# 10_NTC_TEMPSENSOR.net
KiCad netlist of a schematic drawn in Altium Designer
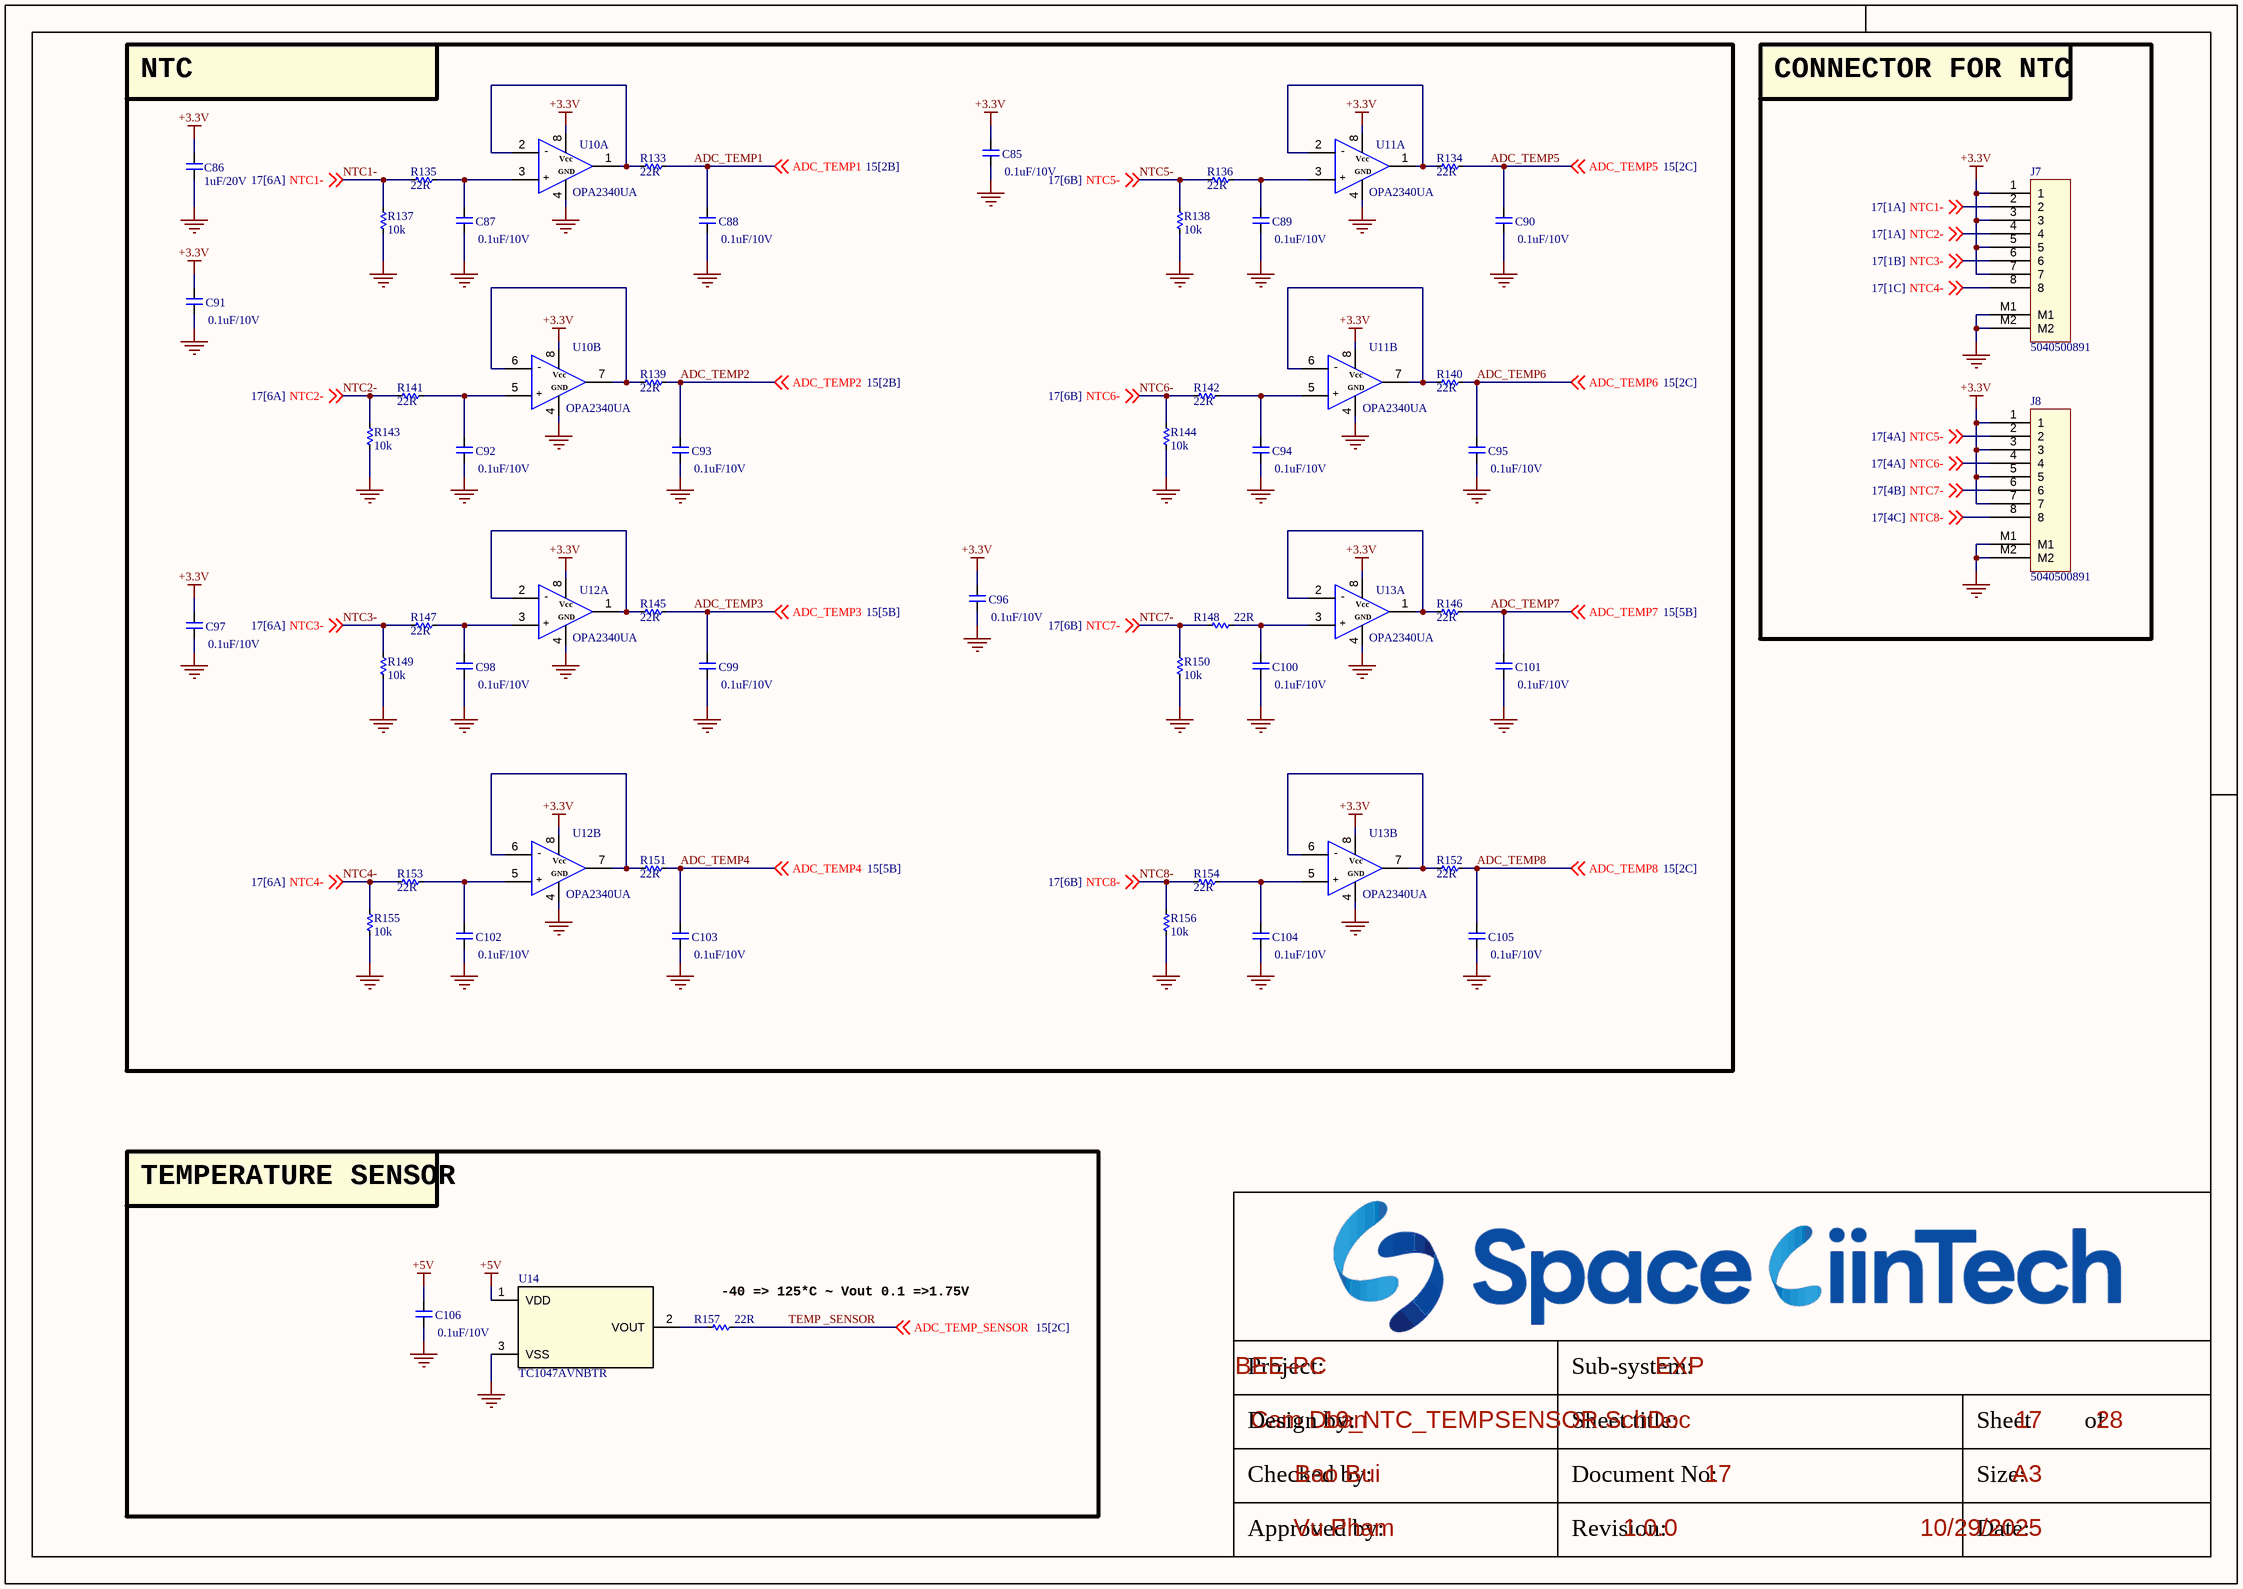
[diagram p0: 10_NTC_TEMPSENSOR.SchDoc]

(export (version "E")
  (design (tool "Eeschema 10.0.6"))
  (components
    (comp (ref "C85")
      (value "0.1uF/10V")
      (footprint "CAP_C_1005X60")
      (description "CAP CHIP")
      (libsource (lib "LABLIB") (part "_CAP_C_2"))
    )
    (comp (ref "C86")
      (value "1uF/20V")
      (footprint "CAP_C_1005X60")
      (description "CAP CHIP")
      (libsource (lib "LABLIB") (part "_CAP_C_2"))
    )
    (comp (ref "C87")
      (value "0.1uF/10V")
      (footprint "CAP_C_1005X60")
      (description "CAP CHIP")
      (libsource (lib "LABLIB") (part "_CAP_C_2"))
    )
    (comp (ref "C88")
      (value "0.1uF/10V")
      (footprint "CAP_C_1005X60")
      (description "CAP CHIP")
      (libsource (lib "LABLIB") (part "_CAP_C_2"))
    )
    (comp (ref "C89")
      (value "0.1uF/10V")
      (footprint "CAP_C_1005X60")
      (description "CAP CHIP")
      (libsource (lib "LABLIB") (part "_CAP_C_2"))
    )
    (comp (ref "C90")
      (value "0.1uF/10V")
      (footprint "CAP_C_1005X60")
      (description "CAP CHIP")
      (libsource (lib "LABLIB") (part "_CAP_C_2"))
    )
    (comp (ref "C91")
      (value "0.1uF/10V")
      (footprint "CAP_C_1005X60")
      (description "CAP CHIP")
      (libsource (lib "LABLIB") (part "_CAP_C_2"))
    )
    (comp (ref "C92")
      (value "0.1uF/10V")
      (footprint "CAP_C_1005X60")
      (description "CAP CHIP")
      (libsource (lib "LABLIB") (part "_CAP_C_2"))
    )
    (comp (ref "C93")
      (value "0.1uF/10V")
      (footprint "CAP_C_1005X60")
      (description "CAP CHIP")
      (libsource (lib "LABLIB") (part "_CAP_C_2"))
    )
    (comp (ref "C94")
      (value "0.1uF/10V")
      (footprint "CAP_C_1005X60")
      (description "CAP CHIP")
      (libsource (lib "LABLIB") (part "_CAP_C_2"))
    )
    (comp (ref "C95")
      (value "0.1uF/10V")
      (footprint "CAP_C_1005X60")
      (description "CAP CHIP")
      (libsource (lib "LABLIB") (part "_CAP_C_2"))
    )
    (comp (ref "C96")
      (value "0.1uF/10V")
      (footprint "CAP_C_1005X60")
      (description "CAP CHIP")
      (libsource (lib "LABLIB") (part "_CAP_C_2"))
    )
    (comp (ref "C97")
      (value "0.1uF/10V")
      (footprint "CAP_C_1005X60")
      (description "CAP CHIP")
      (libsource (lib "LABLIB") (part "_CAP_C_2"))
    )
    (comp (ref "C98")
      (value "0.1uF/10V")
      (footprint "CAP_C_1005X60")
      (description "CAP CHIP")
      (libsource (lib "LABLIB") (part "_CAP_C_2"))
    )
    (comp (ref "C99")
      (value "0.1uF/10V")
      (footprint "CAP_C_1005X60")
      (description "CAP CHIP")
      (libsource (lib "LABLIB") (part "_CAP_C_2"))
    )
    (comp (ref "C100")
      (value "0.1uF/10V")
      (footprint "CAP_C_1005X60")
      (description "CAP CHIP")
      (libsource (lib "LABLIB") (part "_CAP_C_2"))
    )
    (comp (ref "C101")
      (value "0.1uF/10V")
      (footprint "CAP_C_1005X60")
      (description "CAP CHIP")
      (libsource (lib "LABLIB") (part "_CAP_C_2"))
    )
    (comp (ref "C102")
      (value "0.1uF/10V")
      (footprint "CAP_C_1005X60")
      (description "CAP CHIP")
      (libsource (lib "LABLIB") (part "_CAP_C_2"))
    )
    (comp (ref "C103")
      (value "0.1uF/10V")
      (footprint "CAP_C_1005X60")
      (description "CAP CHIP")
      (libsource (lib "LABLIB") (part "_CAP_C_2"))
    )
    (comp (ref "C104")
      (value "0.1uF/10V")
      (footprint "CAP_C_1005X60")
      (description "CAP CHIP")
      (libsource (lib "LABLIB") (part "_CAP_C_2"))
    )
    (comp (ref "C105")
      (value "0.1uF/10V")
      (footprint "CAP_C_1005X60")
      (description "CAP CHIP")
      (libsource (lib "LABLIB") (part "_CAP_C_2"))
    )
    (comp (ref "C106")
      (value "0.1uF/10V")
      (footprint "CAP_C_1005X60")
      (description "CAP CHIP")
      (libsource (lib "LABLIB") (part "_CAP_C_2"))
    )
    (comp (ref "J7")
      (value "5040500891")
      (footprint "MOLEX_5040500891")
      (libsource (lib "LABLIB") (part "Header 8x1_2M"))
    )
    (comp (ref "J8")
      (value "5040500891")
      (footprint "MOLEX_5040500891")
      (libsource (lib "LABLIB") (part "Header 8x1_2M"))
    )
    (comp (ref "R133")
      (value "22R")
      (footprint "RES_C_1005X40")
      (description "RES")
      (libsource (lib "LABLIB") (part "_RES_B_2"))
    )
    (comp (ref "R134")
      (value "22R")
      (footprint "RES_C_1005X40")
      (description "RES")
      (libsource (lib "LABLIB") (part "_RES_B_2"))
    )
    (comp (ref "R135")
      (value "22R")
      (footprint "RES_C_1005X40")
      (description "RES")
      (libsource (lib "LABLIB") (part "_RES_B_2"))
    )
    (comp (ref "R136")
      (value "22R")
      (footprint "RES_C_1005X40")
      (description "RES")
      (libsource (lib "LABLIB") (part "_RES_B_2"))
    )
    (comp (ref "R137")
      (value "10k")
      (footprint "RES_C_1005X40")
      (description "RES")
      (libsource (lib "LABLIB") (part "_RES_B_2"))
    )
    (comp (ref "R138")
      (value "10k")
      (footprint "RES_C_1005X40")
      (description "RES")
      (libsource (lib "LABLIB") (part "_RES_B_2"))
    )
    (comp (ref "R139")
      (value "22R")
      (footprint "RES_C_1005X40")
      (description "RES")
      (libsource (lib "LABLIB") (part "_RES_B_2"))
    )
    (comp (ref "R140")
      (value "22R")
      (footprint "RES_C_1005X40")
      (description "RES")
      (libsource (lib "LABLIB") (part "_RES_B_2"))
    )
    (comp (ref "R141")
      (value "22R")
      (footprint "RES_C_1005X40")
      (description "RES")
      (libsource (lib "LABLIB") (part "_RES_B_2"))
    )
    (comp (ref "R142")
      (value "22R")
      (footprint "RES_C_1005X40")
      (description "RES")
      (libsource (lib "LABLIB") (part "_RES_B_2"))
    )
    (comp (ref "R143")
      (value "10k")
      (footprint "RES_C_1005X40")
      (description "RES")
      (libsource (lib "LABLIB") (part "_RES_B_2"))
    )
    (comp (ref "R144")
      (value "10k")
      (footprint "RES_C_1005X40")
      (description "RES")
      (libsource (lib "LABLIB") (part "_RES_B_2"))
    )
    (comp (ref "R145")
      (value "22R")
      (footprint "RES_C_1005X40")
      (description "RES")
      (libsource (lib "LABLIB") (part "_RES_B_2"))
    )
    (comp (ref "R146")
      (value "22R")
      (footprint "RES_C_1005X40")
      (description "RES")
      (libsource (lib "LABLIB") (part "_RES_B_2"))
    )
    (comp (ref "R147")
      (value "22R")
      (footprint "RES_C_1005X40")
      (description "RES")
      (libsource (lib "LABLIB") (part "_RES_B_2"))
    )
    (comp (ref "R148")
      (value "22R")
      (footprint "RES_C_1005X40")
      (description "RES")
      (libsource (lib "LABLIB") (part "_RES_B_2"))
    )
    (comp (ref "R149")
      (value "10k")
      (footprint "RES_C_1005X40")
      (description "RES")
      (libsource (lib "LABLIB") (part "_RES_B_2"))
    )
    (comp (ref "R150")
      (value "10k")
      (footprint "RES_C_1005X40")
      (description "RES")
      (libsource (lib "LABLIB") (part "_RES_B_2"))
    )
    (comp (ref "R151")
      (value "22R")
      (footprint "RES_C_1005X40")
      (description "RES")
      (libsource (lib "LABLIB") (part "_RES_B_2"))
    )
    (comp (ref "R152")
      (value "22R")
      (footprint "RES_C_1005X40")
      (description "RES")
      (libsource (lib "LABLIB") (part "_RES_B_2"))
    )
    (comp (ref "R153")
      (value "22R")
      (footprint "RES_C_1005X40")
      (description "RES")
      (libsource (lib "LABLIB") (part "_RES_B_2"))
    )
    (comp (ref "R154")
      (value "22R")
      (footprint "RES_C_1005X40")
      (description "RES")
      (libsource (lib "LABLIB") (part "_RES_B_2"))
    )
    (comp (ref "R155")
      (value "10k")
      (footprint "RES_C_1005X40")
      (description "RES")
      (libsource (lib "LABLIB") (part "_RES_B_2"))
    )
    (comp (ref "R156")
      (value "10k")
      (footprint "RES_C_1005X40")
      (description "RES")
      (libsource (lib "LABLIB") (part "_RES_B_2"))
    )
    (comp (ref "R157")
      (value "22R")
      (footprint "RES_C_1005X40")
      (description "RES")
      (libsource (lib "LABLIB") (part "_RES_B_2"))
    )
    (comp (ref "U10")
      (value "OPA2340UA")
      (footprint "SOIC127P602X173-8N")
      (libsource (lib "EXP_HW_V3") (part "OPA2340UA"))
    )
    (comp (ref "U11")
      (value "OPA2340UA")
      (footprint "SOIC127P602X173-8N")
      (libsource (lib "EXP_HW_V3") (part "OPA2340UA"))
    )
    (comp (ref "U12")
      (value "OPA2340UA")
      (footprint "SOIC127P602X173-8N")
      (libsource (lib "EXP_HW_V3") (part "OPA2340UA"))
    )
    (comp (ref "U13")
      (value "OPA2340UA")
      (footprint "SOIC127P602X173-8N")
      (libsource (lib "EXP_HW_V3") (part "OPA2340UA"))
    )
    (comp (ref "U14")
      (value "TC1047AVNBTR")
      (footprint "SOT95P240X120-3N")
      (description "Temperature Sensor Analog, Local -40°C ~ 125°C 10mV/°C SOT-23-3")
      (libsource (lib "LABLIB") (part "IC_SENSOR_TC1047AVNBTR"))
    )
  )
  (nets
    (net (code "1") (name "+3.3V") (class "Default")
      (node (ref "C85") (pin "2") (pinfunction "2_2") (pintype "passive"))
      (node (ref "C86") (pin "2") (pinfunction "2_2") (pintype "passive"))
      (node (ref "C91") (pin "2") (pinfunction "2_2") (pintype "passive"))
      (node (ref "C96") (pin "2") (pinfunction "2_2") (pintype "passive"))
      (node (ref "C97") (pin "2") (pinfunction "2_2") (pintype "passive"))
      (node (ref "J7") (pin "1") (pinfunction "1_1") (pintype "passive"))
      (node (ref "J7") (pin "3") (pinfunction "3_3") (pintype "passive"))
      (node (ref "J7") (pin "5") (pinfunction "5_5") (pintype "passive"))
      (node (ref "J7") (pin "7") (pinfunction "7_7") (pintype "passive"))
      (node (ref "J8") (pin "1") (pinfunction "1_1") (pintype "passive"))
      (node (ref "J8") (pin "3") (pinfunction "3_3") (pintype "passive"))
      (node (ref "J8") (pin "5") (pinfunction "5_5") (pintype "passive"))
      (node (ref "J8") (pin "7") (pinfunction "7_7") (pintype "passive"))
      (node (ref "U10") (pin "8") (pinfunction "8_8") (pintype "passive"))
      (node (ref "U11") (pin "8") (pinfunction "8_8") (pintype "passive"))
      (node (ref "U12") (pin "8") (pinfunction "8_8") (pintype "passive"))
      (node (ref "U13") (pin "8") (pinfunction "8_8") (pintype "passive"))
    )
    (net (code "2") (name "+5V") (class "Default")
      (node (ref "C106") (pin "2") (pinfunction "2_2") (pintype "passive"))
      (node (ref "U14") (pin "1") (pinfunction "VDD_1") (pintype "passive"))
    )
    (net (code "3") (name "ADC_TEMP1") (class "Default")
      (node (ref "C88") (pin "2") (pinfunction "2_2") (pintype "passive"))
      (node (ref "R133") (pin "2") (pinfunction "2_2") (pintype "passive"))
    )
    (net (code "4") (name "ADC_TEMP2") (class "Default")
      (node (ref "C93") (pin "2") (pinfunction "2_2") (pintype "passive"))
      (node (ref "R139") (pin "2") (pinfunction "2_2") (pintype "passive"))
    )
    (net (code "5") (name "ADC_TEMP3") (class "Default")
      (node (ref "C99") (pin "2") (pinfunction "2_2") (pintype "passive"))
      (node (ref "R145") (pin "2") (pinfunction "2_2") (pintype "passive"))
    )
    (net (code "6") (name "ADC_TEMP4") (class "Default")
      (node (ref "C103") (pin "2") (pinfunction "2_2") (pintype "passive"))
      (node (ref "R151") (pin "2") (pinfunction "2_2") (pintype "passive"))
    )
    (net (code "7") (name "ADC_TEMP5") (class "Default")
      (node (ref "C90") (pin "2") (pinfunction "2_2") (pintype "passive"))
      (node (ref "R134") (pin "2") (pinfunction "2_2") (pintype "passive"))
    )
    (net (code "8") (name "ADC_TEMP6") (class "Default")
      (node (ref "C95") (pin "2") (pinfunction "2_2") (pintype "passive"))
      (node (ref "R140") (pin "2") (pinfunction "2_2") (pintype "passive"))
    )
    (net (code "9") (name "ADC_TEMP7") (class "Default")
      (node (ref "C101") (pin "2") (pinfunction "2_2") (pintype "passive"))
      (node (ref "R146") (pin "2") (pinfunction "2_2") (pintype "passive"))
    )
    (net (code "10") (name "ADC_TEMP8") (class "Default")
      (node (ref "C105") (pin "2") (pinfunction "2_2") (pintype "passive"))
      (node (ref "R152") (pin "2") (pinfunction "2_2") (pintype "passive"))
    )
    (net (code "11") (name "ADC_TEMP_SENSOR") (class "Default")
      (node (ref "R157") (pin "2") (pinfunction "2_2") (pintype "passive"))
    )
    (net (code "12") (name "GND") (class "Default")
      (node (ref "C100") (pin "1") (pinfunction "1_1") (pintype "passive"))
      (node (ref "C101") (pin "1") (pinfunction "1_1") (pintype "passive"))
      (node (ref "C102") (pin "1") (pinfunction "1_1") (pintype "passive"))
      (node (ref "C103") (pin "1") (pinfunction "1_1") (pintype "passive"))
      (node (ref "C104") (pin "1") (pinfunction "1_1") (pintype "passive"))
      (node (ref "C105") (pin "1") (pinfunction "1_1") (pintype "passive"))
      (node (ref "C106") (pin "1") (pinfunction "1_1") (pintype "passive"))
      (node (ref "C85") (pin "1") (pinfunction "1_1") (pintype "passive"))
      (node (ref "C86") (pin "1") (pinfunction "1_1") (pintype "passive"))
      (node (ref "C87") (pin "1") (pinfunction "1_1") (pintype "passive"))
      (node (ref "C88") (pin "1") (pinfunction "1_1") (pintype "passive"))
      (node (ref "C89") (pin "1") (pinfunction "1_1") (pintype "passive"))
      (node (ref "C90") (pin "1") (pinfunction "1_1") (pintype "passive"))
      (node (ref "C91") (pin "1") (pinfunction "1_1") (pintype "passive"))
      (node (ref "C92") (pin "1") (pinfunction "1_1") (pintype "passive"))
      (node (ref "C93") (pin "1") (pinfunction "1_1") (pintype "passive"))
      (node (ref "C94") (pin "1") (pinfunction "1_1") (pintype "passive"))
      (node (ref "C95") (pin "1") (pinfunction "1_1") (pintype "passive"))
      (node (ref "C96") (pin "1") (pinfunction "1_1") (pintype "passive"))
      (node (ref "C97") (pin "1") (pinfunction "1_1") (pintype "passive"))
      (node (ref "C98") (pin "1") (pinfunction "1_1") (pintype "passive"))
      (node (ref "C99") (pin "1") (pinfunction "1_1") (pintype "passive"))
      (node (ref "J7") (pin "M1") (pinfunction "M1_M1") (pintype "passive"))
      (node (ref "J7") (pin "M2") (pinfunction "M2_M2") (pintype "passive"))
      (node (ref "J8") (pin "M1") (pinfunction "M1_M1") (pintype "passive"))
      (node (ref "J8") (pin "M2") (pinfunction "M2_M2") (pintype "passive"))
      (node (ref "R137") (pin "1") (pinfunction "1_1") (pintype "passive"))
      (node (ref "R138") (pin "1") (pinfunction "1_1") (pintype "passive"))
      (node (ref "R143") (pin "1") (pinfunction "1_1") (pintype "passive"))
      (node (ref "R144") (pin "1") (pinfunction "1_1") (pintype "passive"))
      (node (ref "R149") (pin "1") (pinfunction "1_1") (pintype "passive"))
      (node (ref "R150") (pin "1") (pinfunction "1_1") (pintype "passive"))
      (node (ref "R155") (pin "1") (pinfunction "1_1") (pintype "passive"))
      (node (ref "R156") (pin "1") (pinfunction "1_1") (pintype "passive"))
      (node (ref "U10") (pin "4") (pinfunction "4_4") (pintype "passive"))
      (node (ref "U11") (pin "4") (pinfunction "4_4") (pintype "passive"))
      (node (ref "U12") (pin "4") (pinfunction "4_4") (pintype "passive"))
      (node (ref "U13") (pin "4") (pinfunction "4_4") (pintype "passive"))
      (node (ref "U14") (pin "3") (pinfunction "VSS_3") (pintype "passive"))
    )
    (net (code "13") (name "NTC1-") (class "Default")
      (node (ref "J7") (pin "2") (pinfunction "2_2") (pintype "passive"))
      (node (ref "R135") (pin "1") (pinfunction "1_1") (pintype "passive"))
      (node (ref "R137") (pin "2") (pinfunction "2_2") (pintype "passive"))
    )
    (net (code "14") (name "NTC2-") (class "Default")
      (node (ref "J7") (pin "4") (pinfunction "4_4") (pintype "passive"))
      (node (ref "R141") (pin "1") (pinfunction "1_1") (pintype "passive"))
      (node (ref "R143") (pin "2") (pinfunction "2_2") (pintype "passive"))
    )
    (net (code "15") (name "NTC3-") (class "Default")
      (node (ref "J7") (pin "6") (pinfunction "6_6") (pintype "passive"))
      (node (ref "R147") (pin "1") (pinfunction "1_1") (pintype "passive"))
      (node (ref "R149") (pin "2") (pinfunction "2_2") (pintype "passive"))
    )
    (net (code "16") (name "NTC4-") (class "Default")
      (node (ref "J7") (pin "8") (pinfunction "8_8") (pintype "passive"))
      (node (ref "R153") (pin "1") (pinfunction "1_1") (pintype "passive"))
      (node (ref "R155") (pin "2") (pinfunction "2_2") (pintype "passive"))
    )
    (net (code "17") (name "NTC5-") (class "Default")
      (node (ref "J8") (pin "2") (pinfunction "2_2") (pintype "passive"))
      (node (ref "R136") (pin "1") (pinfunction "1_1") (pintype "passive"))
      (node (ref "R138") (pin "2") (pinfunction "2_2") (pintype "passive"))
    )
    (net (code "18") (name "NTC6-") (class "Default")
      (node (ref "J8") (pin "4") (pinfunction "4_4") (pintype "passive"))
      (node (ref "R142") (pin "1") (pinfunction "1_1") (pintype "passive"))
      (node (ref "R144") (pin "2") (pinfunction "2_2") (pintype "passive"))
    )
    (net (code "19") (name "NTC7-") (class "Default")
      (node (ref "J8") (pin "6") (pinfunction "6_6") (pintype "passive"))
      (node (ref "R148") (pin "1") (pinfunction "1_1") (pintype "passive"))
      (node (ref "R150") (pin "2") (pinfunction "2_2") (pintype "passive"))
    )
    (net (code "20") (name "NTC8-") (class "Default")
      (node (ref "J8") (pin "8") (pinfunction "8_8") (pintype "passive"))
      (node (ref "R154") (pin "1") (pinfunction "1_1") (pintype "passive"))
      (node (ref "R156") (pin "2") (pinfunction "2_2") (pintype "passive"))
    )
    (net (code "21") (name "Net-(C87-Pad2)") (class "Default")
      (node (ref "C87") (pin "2") (pinfunction "2_2") (pintype "passive"))
      (node (ref "R135") (pin "2") (pinfunction "2_2") (pintype "passive"))
      (node (ref "U10") (pin "3") (pinfunction "3_3") (pintype "passive"))
    )
    (net (code "22") (name "Net-(C89-Pad2)") (class "Default")
      (node (ref "C89") (pin "2") (pinfunction "2_2") (pintype "passive"))
      (node (ref "R136") (pin "2") (pinfunction "2_2") (pintype "passive"))
      (node (ref "U11") (pin "3") (pinfunction "3_3") (pintype "passive"))
    )
    (net (code "23") (name "Net-(C92-Pad2)") (class "Default")
      (node (ref "C92") (pin "2") (pinfunction "2_2") (pintype "passive"))
      (node (ref "R141") (pin "2") (pinfunction "2_2") (pintype "passive"))
      (node (ref "U10") (pin "5") (pinfunction "5_5") (pintype "passive"))
    )
    (net (code "24") (name "Net-(C94-Pad2)") (class "Default")
      (node (ref "C94") (pin "2") (pinfunction "2_2") (pintype "passive"))
      (node (ref "R142") (pin "2") (pinfunction "2_2") (pintype "passive"))
      (node (ref "U11") (pin "5") (pinfunction "5_5") (pintype "passive"))
    )
    (net (code "25") (name "Net-(C98-Pad2)") (class "Default")
      (node (ref "C98") (pin "2") (pinfunction "2_2") (pintype "passive"))
      (node (ref "R147") (pin "2") (pinfunction "2_2") (pintype "passive"))
      (node (ref "U12") (pin "3") (pinfunction "3_3") (pintype "passive"))
    )
    (net (code "26") (name "Net-(C100-Pad2)") (class "Default")
      (node (ref "C100") (pin "2") (pinfunction "2_2") (pintype "passive"))
      (node (ref "R148") (pin "2") (pinfunction "2_2") (pintype "passive"))
      (node (ref "U13") (pin "3") (pinfunction "3_3") (pintype "passive"))
    )
    (net (code "27") (name "Net-(C102-Pad2)") (class "Default")
      (node (ref "C102") (pin "2") (pinfunction "2_2") (pintype "passive"))
      (node (ref "R153") (pin "2") (pinfunction "2_2") (pintype "passive"))
      (node (ref "U12") (pin "5") (pinfunction "5_5") (pintype "passive"))
    )
    (net (code "28") (name "Net-(C104-Pad2)") (class "Default")
      (node (ref "C104") (pin "2") (pinfunction "2_2") (pintype "passive"))
      (node (ref "R154") (pin "2") (pinfunction "2_2") (pintype "passive"))
      (node (ref "U13") (pin "5") (pinfunction "5_5") (pintype "passive"))
    )
    (net (code "29") (name "Net-(R133-Pad1)") (class "Default")
      (node (ref "R133") (pin "1") (pinfunction "1_1") (pintype "passive"))
      (node (ref "U10") (pin "1") (pinfunction "1_1") (pintype "passive"))
      (node (ref "U10") (pin "2") (pinfunction "2_2") (pintype "passive"))
    )
    (net (code "30") (name "Net-(R134-Pad1)") (class "Default")
      (node (ref "R134") (pin "1") (pinfunction "1_1") (pintype "passive"))
      (node (ref "U11") (pin "1") (pinfunction "1_1") (pintype "passive"))
      (node (ref "U11") (pin "2") (pinfunction "2_2") (pintype "passive"))
    )
    (net (code "31") (name "Net-(R139-Pad1)") (class "Default")
      (node (ref "R139") (pin "1") (pinfunction "1_1") (pintype "passive"))
      (node (ref "U10") (pin "6") (pinfunction "6_6") (pintype "passive"))
      (node (ref "U10") (pin "7") (pinfunction "7_7") (pintype "passive"))
    )
    (net (code "32") (name "Net-(R140-Pad1)") (class "Default")
      (node (ref "R140") (pin "1") (pinfunction "1_1") (pintype "passive"))
      (node (ref "U11") (pin "6") (pinfunction "6_6") (pintype "passive"))
      (node (ref "U11") (pin "7") (pinfunction "7_7") (pintype "passive"))
    )
    (net (code "33") (name "Net-(R145-Pad1)") (class "Default")
      (node (ref "R145") (pin "1") (pinfunction "1_1") (pintype "passive"))
      (node (ref "U12") (pin "1") (pinfunction "1_1") (pintype "passive"))
      (node (ref "U12") (pin "2") (pinfunction "2_2") (pintype "passive"))
    )
    (net (code "34") (name "Net-(R146-Pad1)") (class "Default")
      (node (ref "R146") (pin "1") (pinfunction "1_1") (pintype "passive"))
      (node (ref "U13") (pin "1") (pinfunction "1_1") (pintype "passive"))
      (node (ref "U13") (pin "2") (pinfunction "2_2") (pintype "passive"))
    )
    (net (code "35") (name "Net-(R151-Pad1)") (class "Default")
      (node (ref "R151") (pin "1") (pinfunction "1_1") (pintype "passive"))
      (node (ref "U12") (pin "6") (pinfunction "6_6") (pintype "passive"))
      (node (ref "U12") (pin "7") (pinfunction "7_7") (pintype "passive"))
    )
    (net (code "36") (name "Net-(R152-Pad1)") (class "Default")
      (node (ref "R152") (pin "1") (pinfunction "1_1") (pintype "passive"))
      (node (ref "U13") (pin "6") (pinfunction "6_6") (pintype "passive"))
      (node (ref "U13") (pin "7") (pinfunction "7_7") (pintype "passive"))
    )
    (net (code "37") (name "Net-(U14-VOUT)") (class "Default")
      (node (ref "R157") (pin "1") (pinfunction "1_1") (pintype "passive"))
      (node (ref "U14") (pin "2") (pinfunction "VOUT_2") (pintype "passive"))
    )
  )
)
